# gsm_LoRa_due.net
KiCad netlist of a schematic drawn in EAGLE
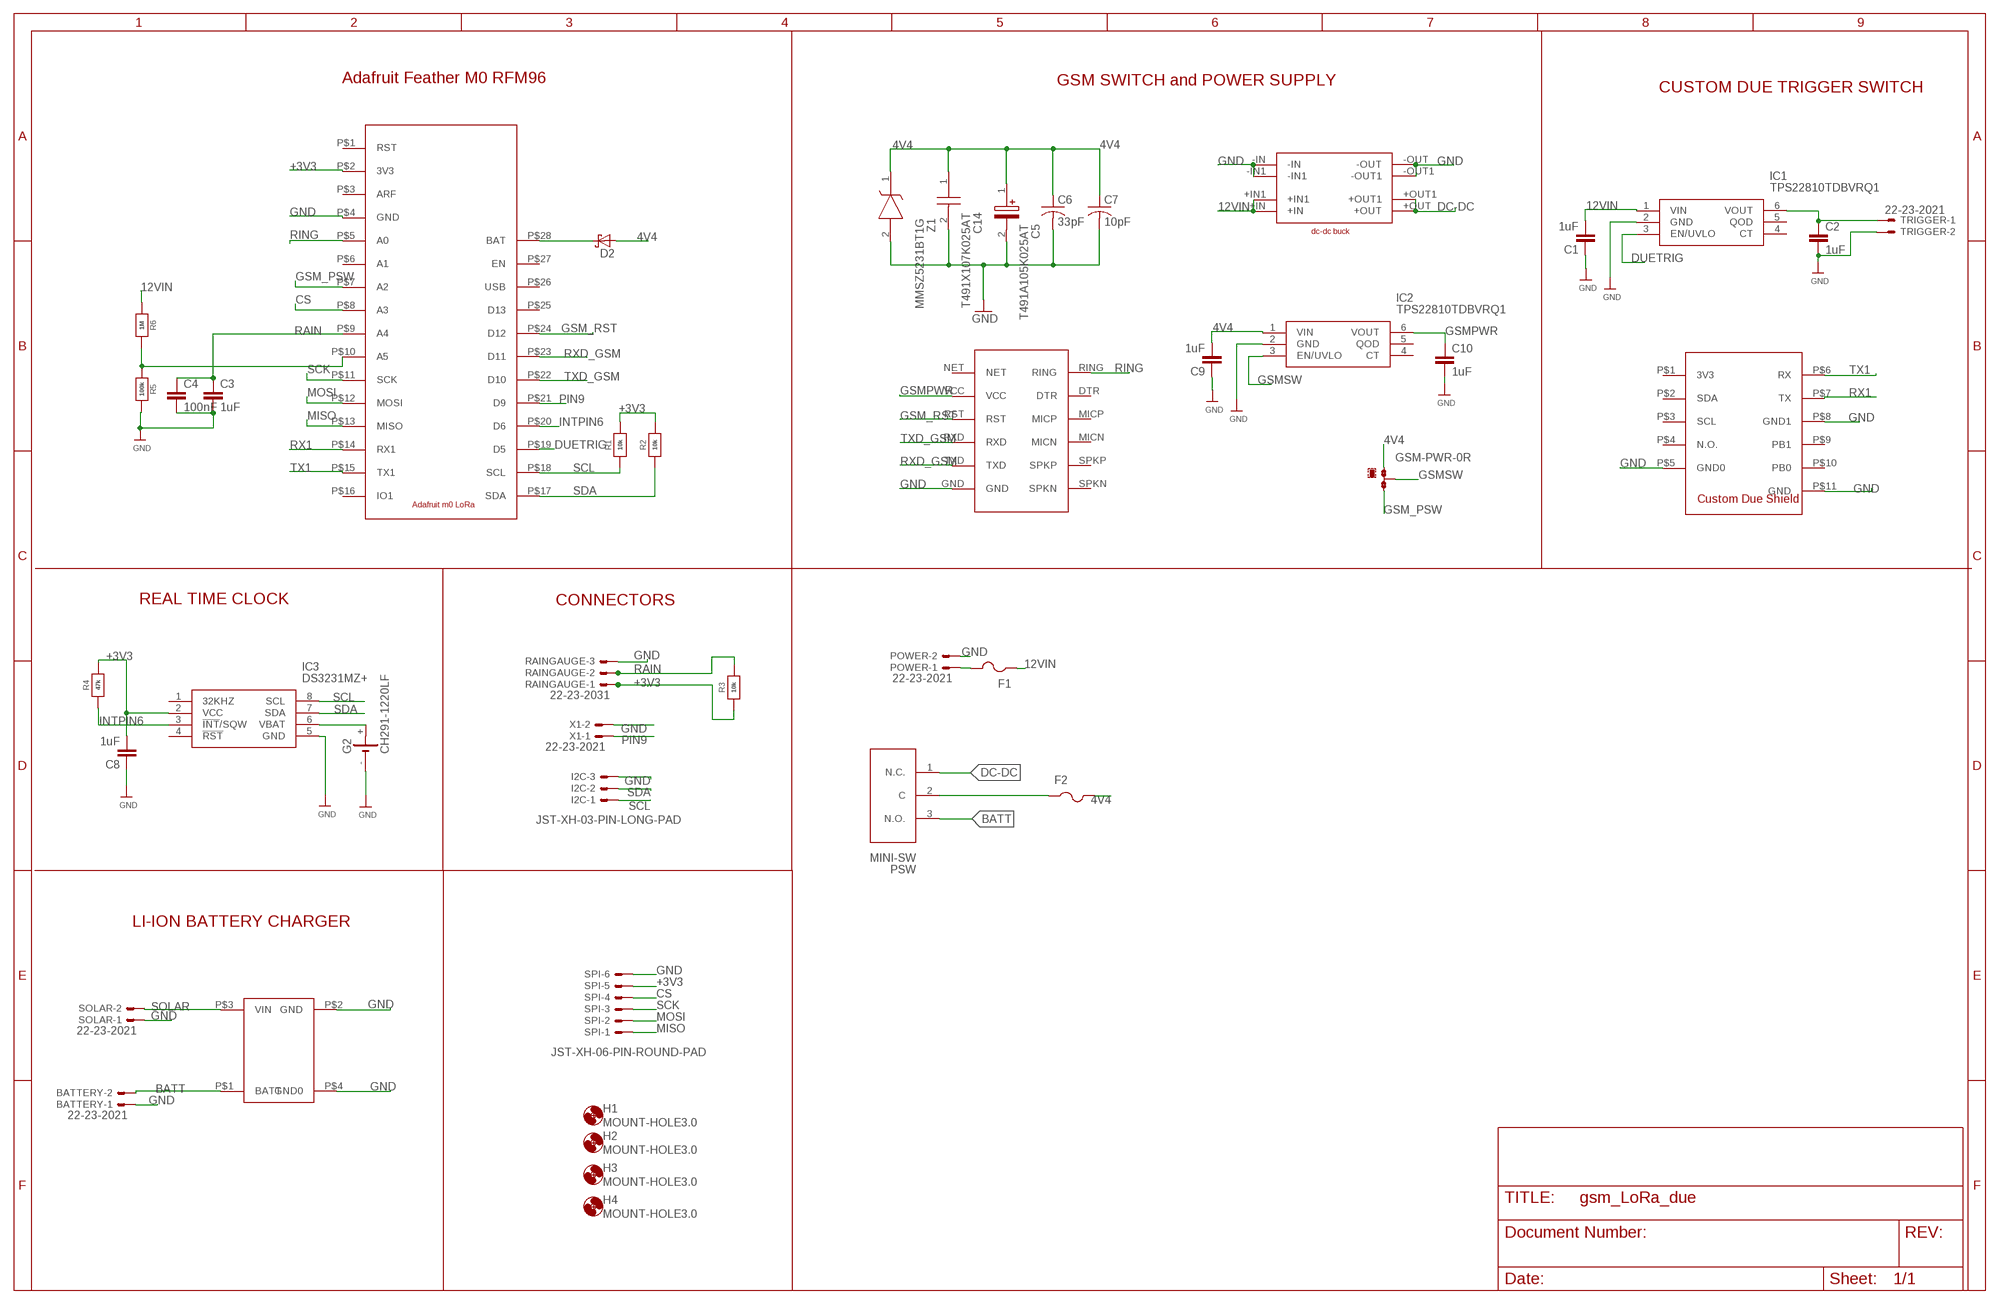
[diagram p0: schematic, sheet 1]

(export (version "E")
  (design (tool "Eeschema 10.0.6"))
  (components
    (comp (ref "BATTERY")
      (value "22-23-2021")
      (footprint "eagle-import:22-23-2021")
      (fields (field (name "MF") "MOLEX"))
      (libsource (lib "eagle-import") (part "22-23-2021"))
    )
    (comp (ref "C1")
      (value "1uF")
      (footprint "eagle-import:C0603")
      (libsource (lib "eagle-import") (part "CC0603"))
    )
    (comp (ref "C2")
      (value "1uF")
      (footprint "eagle-import:C0603")
      (libsource (lib "eagle-import") (part "CC0603"))
    )
    (comp (ref "C3")
      (value "1uF")
      (footprint "eagle-import:C0603")
      (libsource (lib "eagle-import") (part "CC0603"))
    )
    (comp (ref "C4")
      (value "100nF")
      (footprint "eagle-import:C0603")
      (libsource (lib "eagle-import") (part "CC0603"))
    )
    (comp (ref "C5")
      (value "T491A105K025AT")
      (footprint "eagle-import:CAPPM3216X180N")
      (fields (field (name "RS_PART_NUMBER") "8685769"))
      (libsource (lib "eagle-import") (part "T491A105K025AT"))
    )
    (comp (ref "C6")
      (value "33pF")
      (footprint "eagle-import:C0603")
      (libsource (lib "eagle-import") (part "C-USC0603"))
    )
    (comp (ref "C7")
      (value "10pF")
      (footprint "eagle-import:C0603")
      (libsource (lib "eagle-import") (part "C-USC0603"))
    )
    (comp (ref "C8")
      (value "1uF")
      (footprint "eagle-import:C0603")
      (libsource (lib "eagle-import") (part "CC0603"))
    )
    (comp (ref "C9")
      (value "1uF")
      (footprint "eagle-import:C0603")
      (libsource (lib "eagle-import") (part "CC0603"))
    )
    (comp (ref "C10")
      (value "1uF")
      (footprint "eagle-import:C0603")
      (libsource (lib "eagle-import") (part "CC0603"))
    )
    (comp (ref "C14")
      (value "T491X107K025AT")
      (footprint "eagle-import:CAPPM7343X430N")
      (fields (field (name "RS_PART_NUMBER") "8015511P"))
      (libsource (lib "eagle-import") (part "T491X107K025AT"))
    )
    (comp (ref "D2")
      (value "SCHOTTKY-DIODE")
      (footprint "eagle-import:DIODE_SMB")
      (libsource (lib "eagle-import") (part "SCHOTTKY-DIODE"))
    )
    (comp (ref "F1")
      (value "PTCFUSE-1206")
      (footprint "eagle-import:R1206")
      (libsource (lib "eagle-import") (part "PTCFUSE-1206"))
    )
    (comp (ref "F2")
      (value "PTCFUSE-1206")
      (footprint "eagle-import:R1206")
      (libsource (lib "eagle-import") (part "PTCFUSE-1206"))
    )
    (comp (ref "G2")
      (value "CH291-1220LF")
      (footprint "eagle-import:CH291-1220LF")
      (libsource (lib "eagle-import") (part "CH291-1220LF"))
    )
    (comp (ref "GSM-PWR")
      (value "0R-JUMPB")
      (footprint "eagle-import:B0R-JMP")
      (libsource (lib "eagle-import") (part "0R-JUMPB"))
    )
    (comp (ref "H1")
      (value "MOUNT-HOLE3.0")
      (footprint "eagle-import:3,0")
      (libsource (lib "eagle-import") (part "MOUNT-HOLE3.0"))
    )
    (comp (ref "H2")
      (value "MOUNT-HOLE3.0")
      (footprint "eagle-import:3,0")
      (libsource (lib "eagle-import") (part "MOUNT-HOLE3.0"))
    )
    (comp (ref "H3")
      (value "MOUNT-HOLE3.0")
      (footprint "eagle-import:3,0")
      (libsource (lib "eagle-import") (part "MOUNT-HOLE3.0"))
    )
    (comp (ref "H4")
      (value "MOUNT-HOLE3.0")
      (footprint "eagle-import:3,0")
      (libsource (lib "eagle-import") (part "MOUNT-HOLE3.0"))
    )
    (comp (ref "I2C")
      (value "JST-XH-03-PIN-LONG-PAD")
      (footprint "eagle-import:JST-XH-03-PACKAGE-LONG-PAD")
      (libsource (lib "eagle-import") (part "JST-XH-03-PIN-LONG-PAD"))
    )
    (comp (ref "IC1")
      (value "TPS22810TDBVRQ1")
      (footprint "eagle-import:SOT95P280X145-6N")
      (libsource (lib "eagle-import") (part "TPS22810TDBVRQ1"))
    )
    (comp (ref "IC2")
      (value "TPS22810TDBVRQ1")
      (footprint "eagle-import:SOT95P280X145-6N")
      (libsource (lib "eagle-import") (part "TPS22810TDBVRQ1"))
    )
    (comp (ref "IC3")
      (value "DS3231MZ+")
      (footprint "eagle-import:SOIC127P600X175-8N")
      (fields (field (name "RS_PART_NUMBER") "1897249"))
      (libsource (lib "eagle-import") (part "DS3231MZ+"))
    )
    (comp (ref "POWER")
      (value "22-23-2021")
      (footprint "eagle-import:22-23-2021")
      (fields (field (name "MF") "MOLEX"))
      (libsource (lib "eagle-import") (part "22-23-2021"))
    )
    (comp (ref "PSW")
      (value "MINI-SW")
      (footprint "eagle-import:MINI-SW")
      (libsource (lib "eagle-import") (part "MINI-SW"))
    )
    (comp (ref "R1")
      (value "10k")
      (footprint "eagle-import:0603-NO")
      (libsource (lib "eagle-import") (part "RESISTOR_0603_NOOUT"))
    )
    (comp (ref "R2")
      (value "10k")
      (footprint "eagle-import:0603-NO")
      (libsource (lib "eagle-import") (part "RESISTOR_0603_NOOUT"))
    )
    (comp (ref "R3")
      (value "10k")
      (footprint "eagle-import:0603-NO")
      (libsource (lib "eagle-import") (part "RESISTOR_0603_NOOUT"))
    )
    (comp (ref "R4")
      (value "47k")
      (footprint "eagle-import:0603-NO")
      (libsource (lib "eagle-import") (part "RESISTOR_0603_NOOUT"))
    )
    (comp (ref "R5")
      (value "100k")
      (footprint "eagle-import:0603-NO")
      (libsource (lib "eagle-import") (part "RESISTOR_0603_NOOUT"))
    )
    (comp (ref "R6")
      (value "1M")
      (footprint "eagle-import:0603-NO")
      (libsource (lib "eagle-import") (part "RESISTOR_0603_NOOUT"))
    )
    (comp (ref "RAINGAUGE")
      (value "22-23-2031")
      (footprint "eagle-import:22-23-2031")
      (fields (field (name "MF") "MOLEX"))
      (libsource (lib "eagle-import") (part "22-23-2031"))
    )
    (comp (ref "SOLAR")
      (value "22-23-2021")
      (footprint "eagle-import:22-23-2021")
      (fields (field (name "MF") "MOLEX"))
      (libsource (lib "eagle-import") (part "22-23-2021"))
    )
    (comp (ref "SPI")
      (value "JST-XH-06-PIN-ROUND-PAD")
      (footprint "eagle-import:JST-XH-06-PACKAGE-ROUND-PAD")
      (libsource (lib "eagle-import") (part "JST-XH-06-PIN-ROUND-PAD"))
    )
    (comp (ref "TRIGGER")
      (value "22-23-2021")
      (footprint "eagle-import:22-23-2021")
      (fields (field (name "MF") "MOLEX"))
      (libsource (lib "eagle-import") (part "22-23-2021"))
    )
    (comp (ref "U$1")
      (value "M0_LORA")
      (footprint "eagle-import:RFM69")
      (libsource (lib "eagle-import") (part "M0_LORA"))
    )
    (comp (ref "U$8")
      (value "DUE_PADSDUE_GSM")
      (footprint "eagle-import:DUESHIELD_BIG")
      (libsource (lib "eagle-import") (part "DUE_PADSDUE_GSM"))
    )
    (comp (ref "U$9")
      (value "SIM800L_MODULE")
      (footprint "eagle-import:SIM800L")
      (libsource (lib "eagle-import") (part "SIM800L_MODULE"))
    )
    (comp (ref "U$10")
      (value "DC-DC_BUCK_MAD")
      (footprint "eagle-import:DC-DC_BUCK")
      (libsource (lib "eagle-import") (part "DC-DC_BUCK_MAD"))
    )
    (comp (ref "U$11")
      (value "LI-ION-CHARGER")
      (footprint "eagle-import:LI-ION")
      (libsource (lib "eagle-import") (part "LI-ION-CHARGER"))
    )
    (comp (ref "X1")
      (value "22-23-2021")
      (footprint "eagle-import:22-23-2021")
      (fields (field (name "MF") "MOLEX"))
      (libsource (lib "eagle-import") (part "22-23-2021"))
    )
    (comp (ref "Z1")
      (value "MMSZ5231BT1G")
      (footprint "eagle-import:SOD3716X135N")
      (fields (field (name "RS_PART_NUMBER") "5453049P"))
      (libsource (lib "eagle-import") (part "MMSZ5231BT1G"))
    )
  )
  (nets
    (net (code "1") (name "/+3V3") (class "Default")
      (node (ref "C8") (pin "2") (pinfunction "2_2") (pintype "passive"))
      (node (ref "IC3") (pin "2") (pinfunction "VCC_2") (pintype "power_in"))
      (node (ref "R1") (pin "2") (pinfunction "2_2") (pintype "passive"))
      (node (ref "R2") (pin "2") (pinfunction "2_2") (pintype "passive"))
      (node (ref "R3") (pin "1") (pinfunction "1_1") (pintype "passive"))
      (node (ref "R4") (pin "2") (pinfunction "2_2") (pintype "passive"))
      (node (ref "RAINGAUGE") (pin "1") (pinfunction "S_1") (pintype "passive"))
      (node (ref "SPI") (pin "5") (pinfunction "S_5") (pintype "passive"))
      (node (ref "U$1") (pin "P$2") (pinfunction "3V3_P$2") (pintype "bidirectional"))
    )
    (net (code "2") (name "/4V4") (class "Default")
      (node (ref "C14") (pin "1") (pinfunction "1_1") (pintype "bidirectional"))
      (node (ref "C5") (pin "1") (pinfunction "+_1") (pintype "bidirectional"))
      (node (ref "C6") (pin "1") (pinfunction "1_1") (pintype "passive"))
      (node (ref "C7") (pin "1") (pinfunction "1_1") (pintype "passive"))
      (node (ref "C9") (pin "2") (pinfunction "2_2") (pintype "passive"))
      (node (ref "D2") (pin "A") (pinfunction "C_A") (pintype "passive"))
      (node (ref "F2") (pin "2") (pinfunction "2_2") (pintype "passive"))
      (node (ref "GSM-PWR") (pin "1") (pinfunction "1_1") (pintype "passive"))
      (node (ref "IC2") (pin "1") (pinfunction "VIN_1") (pintype "bidirectional"))
      (node (ref "Z1") (pin "1") (pinfunction "K_1") (pintype "bidirectional"))
    )
    (net (code "3") (name "/12VIN") (class "Default")
      (node (ref "C1") (pin "2") (pinfunction "2_2") (pintype "passive"))
      (node (ref "F1") (pin "1") (pinfunction "1_1") (pintype "passive"))
      (node (ref "IC1") (pin "1") (pinfunction "VIN_1") (pintype "bidirectional"))
      (node (ref "R6") (pin "1") (pinfunction "1_1") (pintype "passive"))
      (node (ref "U$10") (pin "+IN") (pinfunction "+IN_+IN") (pintype "bidirectional"))
      (node (ref "U$10") (pin "+IN1") (pinfunction "+IN1_+IN1") (pintype "bidirectional"))
    )
    (net (code "4") (name "/CS") (class "Default")
      (node (ref "SPI") (pin "4") (pinfunction "S_4") (pintype "passive"))
      (node (ref "U$1") (pin "P$8") (pinfunction "A3_P$8") (pintype "bidirectional"))
    )
    (net (code "5") (name "/DUETRIG") (class "Default")
      (node (ref "IC1") (pin "3") (pinfunction "EN/UVLO_3") (pintype "bidirectional"))
      (node (ref "U$1") (pin "P$19") (pinfunction "D5_P$19") (pintype "bidirectional"))
    )
    (net (code "6") (name "/GSMPWR") (class "Default")
      (node (ref "C10") (pin "1") (pinfunction "1_1") (pintype "passive"))
      (node (ref "IC2") (pin "6") (pinfunction "VOUT_6") (pintype "bidirectional"))
      (node (ref "U$9") (pin "VCC") (pinfunction "VCC_VCC") (pintype "bidirectional"))
    )
    (net (code "7") (name "/GSMSW") (class "Default")
      (node (ref "GSM-PWR") (pin "2") (pinfunction "2_2") (pintype "passive"))
      (node (ref "IC2") (pin "3") (pinfunction "EN/UVLO_3") (pintype "bidirectional"))
    )
    (net (code "8") (name "/GSM_PSW") (class "Default")
      (node (ref "GSM-PWR") (pin "3") (pinfunction "3_3") (pintype "passive"))
      (node (ref "U$1") (pin "P$7") (pinfunction "A2_P$7") (pintype "bidirectional"))
    )
    (net (code "9") (name "/GSM_RST") (class "Default")
      (node (ref "U$1") (pin "P$24") (pinfunction "D12_P$24") (pintype "bidirectional"))
      (node (ref "U$9") (pin "RST") (pinfunction "RST_RST") (pintype "bidirectional"))
    )
    (net (code "10") (name "/INTPIN6") (class "Default")
      (node (ref "IC3") (pin "3") (pinfunction "~{INT}/SQW_3") (pintype "input"))
      (node (ref "R4") (pin "1") (pinfunction "1_1") (pintype "passive"))
      (node (ref "U$1") (pin "P$20") (pinfunction "D6_P$20") (pintype "bidirectional"))
    )
    (net (code "11") (name "/MISO") (class "Default")
      (node (ref "SPI") (pin "1") (pinfunction "S_1") (pintype "passive"))
      (node (ref "U$1") (pin "P$13") (pinfunction "MISO_P$13") (pintype "bidirectional"))
    )
    (net (code "12") (name "/MOSI") (class "Default")
      (node (ref "SPI") (pin "2") (pinfunction "S_2") (pintype "passive"))
      (node (ref "U$1") (pin "P$12") (pinfunction "MOSI_P$12") (pintype "bidirectional"))
    )
    (net (code "13") (name "/PIN9") (class "Default")
      (node (ref "U$1") (pin "P$21") (pinfunction "D9_P$21") (pintype "bidirectional"))
      (node (ref "X1") (pin "1") (pinfunction "S_1") (pintype "passive"))
    )
    (net (code "14") (name "/RAIN") (class "Default")
      (node (ref "C3") (pin "1") (pinfunction "1_1") (pintype "passive"))
      (node (ref "C4") (pin "1") (pinfunction "1_1") (pintype "passive"))
      (node (ref "R3") (pin "2") (pinfunction "2_2") (pintype "passive"))
      (node (ref "RAINGAUGE") (pin "2") (pinfunction "S_2") (pintype "passive"))
      (node (ref "U$1") (pin "P$9") (pinfunction "A4_P$9") (pintype "bidirectional"))
    )
    (net (code "15") (name "/RING") (class "Default")
      (node (ref "U$1") (pin "P$5") (pinfunction "A0_P$5") (pintype "bidirectional"))
      (node (ref "U$9") (pin "RING") (pinfunction "RING_RING") (pintype "bidirectional"))
    )
    (net (code "16") (name "/RX1") (class "Default")
      (node (ref "U$1") (pin "P$14") (pinfunction "RX1_P$14") (pintype "bidirectional"))
      (node (ref "U$8") (pin "P$7") (pinfunction "TX_P$7") (pintype "bidirectional"))
    )
    (net (code "17") (name "/RXD_GSM") (class "Default")
      (node (ref "U$1") (pin "P$23") (pinfunction "D11_P$23") (pintype "bidirectional"))
      (node (ref "U$9") (pin "TXD") (pinfunction "TXD_TXD") (pintype "bidirectional"))
    )
    (net (code "18") (name "/SCK") (class "Default")
      (node (ref "SPI") (pin "3") (pinfunction "S_3") (pintype "passive"))
      (node (ref "U$1") (pin "P$11") (pinfunction "SCK_P$11") (pintype "bidirectional"))
    )
    (net (code "19") (name "/SCL") (class "Default")
      (node (ref "I2C") (pin "1") (pinfunction "S_1") (pintype "passive"))
      (node (ref "IC3") (pin "8") (pinfunction "SCL_8") (pintype "bidirectional"))
      (node (ref "R1") (pin "1") (pinfunction "1_1") (pintype "passive"))
      (node (ref "U$1") (pin "P$18") (pinfunction "SCL_P$18") (pintype "bidirectional"))
    )
    (net (code "20") (name "/SDA") (class "Default")
      (node (ref "I2C") (pin "2") (pinfunction "S_2") (pintype "passive"))
      (node (ref "IC3") (pin "7") (pinfunction "SDA_7") (pintype "bidirectional"))
      (node (ref "R2") (pin "1") (pinfunction "1_1") (pintype "passive"))
      (node (ref "U$1") (pin "P$17") (pinfunction "SDA_P$17") (pintype "bidirectional"))
    )
    (net (code "21") (name "/SOLAR") (class "Default")
      (node (ref "SOLAR") (pin "2") (pinfunction "S_2") (pintype "passive"))
      (node (ref "U$11") (pin "P$3") (pinfunction "VIN_P$3") (pintype "bidirectional"))
    )
    (net (code "22") (name "/TX1") (class "Default")
      (node (ref "U$1") (pin "P$15") (pinfunction "TX1_P$15") (pintype "bidirectional"))
      (node (ref "U$8") (pin "P$6") (pinfunction "RX_P$6") (pintype "bidirectional"))
    )
    (net (code "23") (name "/TXD_GSM") (class "Default")
      (node (ref "U$1") (pin "P$22") (pinfunction "D10_P$22") (pintype "bidirectional"))
      (node (ref "U$9") (pin "RXD") (pinfunction "RXD_RXD") (pintype "bidirectional"))
    )
    (net (code "24") (name "BATT") (class "Default")
      (node (ref "BATTERY") (pin "2") (pinfunction "S_2") (pintype "passive"))
      (node (ref "PSW") (pin "3") (pinfunction "N.O._3") (pintype "bidirectional"))
      (node (ref "U$11") (pin "P$1") (pinfunction "BATT_P$1") (pintype "bidirectional"))
    )
    (net (code "25") (name "DC-DC") (class "Default")
      (node (ref "PSW") (pin "1") (pinfunction "N.C._1") (pintype "bidirectional"))
      (node (ref "U$10") (pin "+OUT") (pinfunction "+OUT_+OUT") (pintype "bidirectional"))
      (node (ref "U$10") (pin "+OUT1") (pinfunction "+OUT1_+OUT1") (pintype "bidirectional"))
    )
    (net (code "26") (name "GND") (class "Default")
      (node (ref "BATTERY") (pin "1") (pinfunction "S_1") (pintype "passive"))
      (node (ref "C1") (pin "1") (pinfunction "1_1") (pintype "passive"))
      (node (ref "C10") (pin "2") (pinfunction "2_2") (pintype "passive"))
      (node (ref "C14") (pin "2") (pinfunction "2_2") (pintype "bidirectional"))
      (node (ref "C2") (pin "2") (pinfunction "2_2") (pintype "passive"))
      (node (ref "C3") (pin "2") (pinfunction "2_2") (pintype "passive"))
      (node (ref "C4") (pin "2") (pinfunction "2_2") (pintype "passive"))
      (node (ref "C5") (pin "2") (pinfunction "-_2") (pintype "bidirectional"))
      (node (ref "C6") (pin "2") (pinfunction "2_2") (pintype "passive"))
      (node (ref "C7") (pin "2") (pinfunction "2_2") (pintype "passive"))
      (node (ref "C8") (pin "1") (pinfunction "1_1") (pintype "passive"))
      (node (ref "C9") (pin "1") (pinfunction "1_1") (pintype "passive"))
      (node (ref "G2") (pin "-") (pinfunction "-_-") (pintype "passive"))
      (node (ref "I2C") (pin "3") (pinfunction "S_3") (pintype "passive"))
      (node (ref "IC1") (pin "2") (pinfunction "GND_2") (pintype "bidirectional"))
      (node (ref "IC2") (pin "2") (pinfunction "GND_2") (pintype "bidirectional"))
      (node (ref "IC3") (pin "5") (pinfunction "GND_5") (pintype "power_in"))
      (node (ref "POWER") (pin "2") (pinfunction "S_2") (pintype "passive"))
      (node (ref "R5") (pin "2") (pinfunction "2_2") (pintype "passive"))
      (node (ref "RAINGAUGE") (pin "3") (pinfunction "S_3") (pintype "passive"))
      (node (ref "SOLAR") (pin "1") (pinfunction "S_1") (pintype "passive"))
      (node (ref "SPI") (pin "6") (pinfunction "S_6") (pintype "passive"))
      (node (ref "TRIGGER") (pin "2") (pinfunction "S_2") (pintype "passive"))
      (node (ref "U$1") (pin "P$4") (pinfunction "GND_P$4") (pintype "bidirectional"))
      (node (ref "U$10") (pin "-IN") (pinfunction "-IN_-IN") (pintype "bidirectional"))
      (node (ref "U$10") (pin "-IN1") (pinfunction "-IN1_-IN1") (pintype "bidirectional"))
      (node (ref "U$10") (pin "-OUT") (pinfunction "-OUT_-OUT") (pintype "bidirectional"))
      (node (ref "U$10") (pin "-OUT1") (pinfunction "-OUT1_-OUT1") (pintype "bidirectional"))
      (node (ref "U$11") (pin "P$2") (pinfunction "GND_P$2") (pintype "bidirectional"))
      (node (ref "U$11") (pin "P$4") (pinfunction "GND0_P$4") (pintype "bidirectional"))
      (node (ref "U$8") (pin "P$11") (pinfunction "GND_P$11") (pintype "bidirectional"))
      (node (ref "U$8") (pin "P$5") (pinfunction "GND0_P$5") (pintype "bidirectional"))
      (node (ref "U$8") (pin "P$8") (pinfunction "GND1_P$8") (pintype "bidirectional"))
      (node (ref "U$9") (pin "GND") (pinfunction "GND_GND") (pintype "bidirectional"))
      (node (ref "X1") (pin "2") (pinfunction "S_2") (pintype "passive"))
      (node (ref "Z1") (pin "2") (pinfunction "A_2") (pintype "bidirectional"))
    )
    (net (code "27") (name "Net-(D2-A)") (class "Default")
      (node (ref "D2") (pin "C") (pinfunction "A_C") (pintype "passive"))
      (node (ref "U$1") (pin "P$28") (pinfunction "BAT_P$28") (pintype "bidirectional"))
    )
    (net (code "28") (name "Net-(IC1-VOUT)") (class "Default")
      (node (ref "C2") (pin "1") (pinfunction "1_1") (pintype "passive"))
      (node (ref "IC1") (pin "6") (pinfunction "VOUT_6") (pintype "bidirectional"))
      (node (ref "TRIGGER") (pin "1") (pinfunction "S_1") (pintype "passive"))
    )
    (net (code "29") (name "Net-(IC3-VBAT)") (class "Default")
      (node (ref "G2") (pin "+") (pinfunction "+_+") (pintype "passive"))
      (node (ref "IC3") (pin "6") (pinfunction "VBAT_6") (pintype "bidirectional"))
    )
    (net (code "30") (name "Net-(POWERA-S)") (class "Default")
      (node (ref "F1") (pin "2") (pinfunction "2_2") (pintype "passive"))
      (node (ref "POWER") (pin "1") (pinfunction "S_1") (pintype "passive"))
    )
    (net (code "31") (name "Net-(PSW-C)") (class "Default")
      (node (ref "F2") (pin "1") (pinfunction "1_1") (pintype "passive"))
      (node (ref "PSW") (pin "2") (pinfunction "C_2") (pintype "bidirectional"))
    )
    (net (code "32") (name "Net-(U$1-A5)") (class "Default")
      (node (ref "R5") (pin "1") (pinfunction "1_1") (pintype "passive"))
      (node (ref "R6") (pin "2") (pinfunction "2_2") (pintype "passive"))
      (node (ref "U$1") (pin "P$10") (pinfunction "A5_P$10") (pintype "bidirectional"))
    )
    (net (code "33") (name "unconnected-(IC1-CT-Pad4)") (class "Default")
      (node (ref "IC1") (pin "4") (pinfunction "CT_4") (pintype "bidirectional"))
    )
    (net (code "34") (name "unconnected-(IC1-QOD-Pad5)") (class "Default")
      (node (ref "IC1") (pin "5") (pinfunction "QOD_5") (pintype "bidirectional"))
    )
    (net (code "35") (name "unconnected-(IC2-CT-Pad4)") (class "Default")
      (node (ref "IC2") (pin "4") (pinfunction "CT_4") (pintype "bidirectional"))
    )
    (net (code "36") (name "unconnected-(IC2-QOD-Pad5)") (class "Default")
      (node (ref "IC2") (pin "5") (pinfunction "QOD_5") (pintype "bidirectional"))
    )
    (net (code "37") (name "unconnected-(IC3-32KHZ-Pad1)") (class "Default")
      (node (ref "IC3") (pin "1") (pinfunction "32KHZ_1") (pintype "bidirectional"))
    )
    (net (code "38") (name "unconnected-(IC3-~{RST}-Pad4)") (class "Default")
      (node (ref "IC3") (pin "4") (pinfunction "~{RST}_4") (pintype "input"))
    )
    (net (code "39") (name "unconnected-(U$1-A1-PadP$6)") (class "Default")
      (node (ref "U$1") (pin "P$6") (pinfunction "A1_P$6") (pintype "bidirectional"))
    )
    (net (code "40") (name "unconnected-(U$1-ARF-PadP$3)") (class "Default")
      (node (ref "U$1") (pin "P$3") (pinfunction "ARF_P$3") (pintype "bidirectional"))
    )
    (net (code "41") (name "unconnected-(U$1-D13-PadP$25)") (class "Default")
      (node (ref "U$1") (pin "P$25") (pinfunction "D13_P$25") (pintype "bidirectional"))
    )
    (net (code "42") (name "unconnected-(U$1-EN-PadP$27)") (class "Default")
      (node (ref "U$1") (pin "P$27") (pinfunction "EN_P$27") (pintype "bidirectional"))
    )
    (net (code "43") (name "unconnected-(U$1-IO1-PadP$16)") (class "Default")
      (node (ref "U$1") (pin "P$16") (pinfunction "IO1_P$16") (pintype "bidirectional"))
    )
    (net (code "44") (name "unconnected-(U$1-RST-PadP$1)") (class "Default")
      (node (ref "U$1") (pin "P$1") (pinfunction "RST_P$1") (pintype "bidirectional"))
    )
    (net (code "45") (name "unconnected-(U$1-USB-PadP$26)") (class "Default")
      (node (ref "U$1") (pin "P$26") (pinfunction "USB_P$26") (pintype "bidirectional"))
    )
    (net (code "46") (name "unconnected-(U$8-3V3-PadP$1)") (class "Default")
      (node (ref "U$8") (pin "P$1") (pinfunction "3V3_P$1") (pintype "bidirectional"))
    )
    (net (code "47") (name "unconnected-(U$8-N.O.-PadP$4)") (class "Default")
      (node (ref "U$8") (pin "P$4") (pinfunction "N.O._P$4") (pintype "bidirectional"))
    )
    (net (code "48") (name "unconnected-(U$8-PB0-PadP$10)") (class "Default")
      (node (ref "U$8") (pin "P$10") (pinfunction "PB0_P$10") (pintype "bidirectional"))
    )
    (net (code "49") (name "unconnected-(U$8-PB1-PadP$9)") (class "Default")
      (node (ref "U$8") (pin "P$9") (pinfunction "PB1_P$9") (pintype "bidirectional"))
    )
    (net (code "50") (name "unconnected-(U$8-SCL-PadP$3)") (class "Default")
      (node (ref "U$8") (pin "P$3") (pinfunction "SCL_P$3") (pintype "bidirectional"))
    )
    (net (code "51") (name "unconnected-(U$8-SDA-PadP$2)") (class "Default")
      (node (ref "U$8") (pin "P$2") (pinfunction "SDA_P$2") (pintype "bidirectional"))
    )
    (net (code "52") (name "unconnected-(U$9-PadDTR)") (class "Default")
      (node (ref "U$9") (pin "DTR") (pinfunction "DTR_DTR") (pintype "bidirectional"))
    )
    (net (code "53") (name "unconnected-(U$9-PadMICN)") (class "Default")
      (node (ref "U$9") (pin "MICN") (pinfunction "MICN_MICN") (pintype "bidirectional"))
    )
    (net (code "54") (name "unconnected-(U$9-PadMICP)") (class "Default")
      (node (ref "U$9") (pin "MICP") (pinfunction "MICP_MICP") (pintype "bidirectional"))
    )
    (net (code "55") (name "unconnected-(U$9-PadNET)") (class "Default")
      (node (ref "U$9") (pin "NET") (pinfunction "NET_NET") (pintype "bidirectional"))
    )
    (net (code "56") (name "unconnected-(U$9-PadSPKN)") (class "Default")
      (node (ref "U$9") (pin "SPKN") (pinfunction "SPKN_SPKN") (pintype "bidirectional"))
    )
    (net (code "57") (name "unconnected-(U$9-PadSPKP)") (class "Default")
      (node (ref "U$9") (pin "SPKP") (pinfunction "SPKP_SPKP") (pintype "bidirectional"))
    )
  )
)
